# HF_Amp.net
KiCad netlist of a schematic drawn in Altium Designer
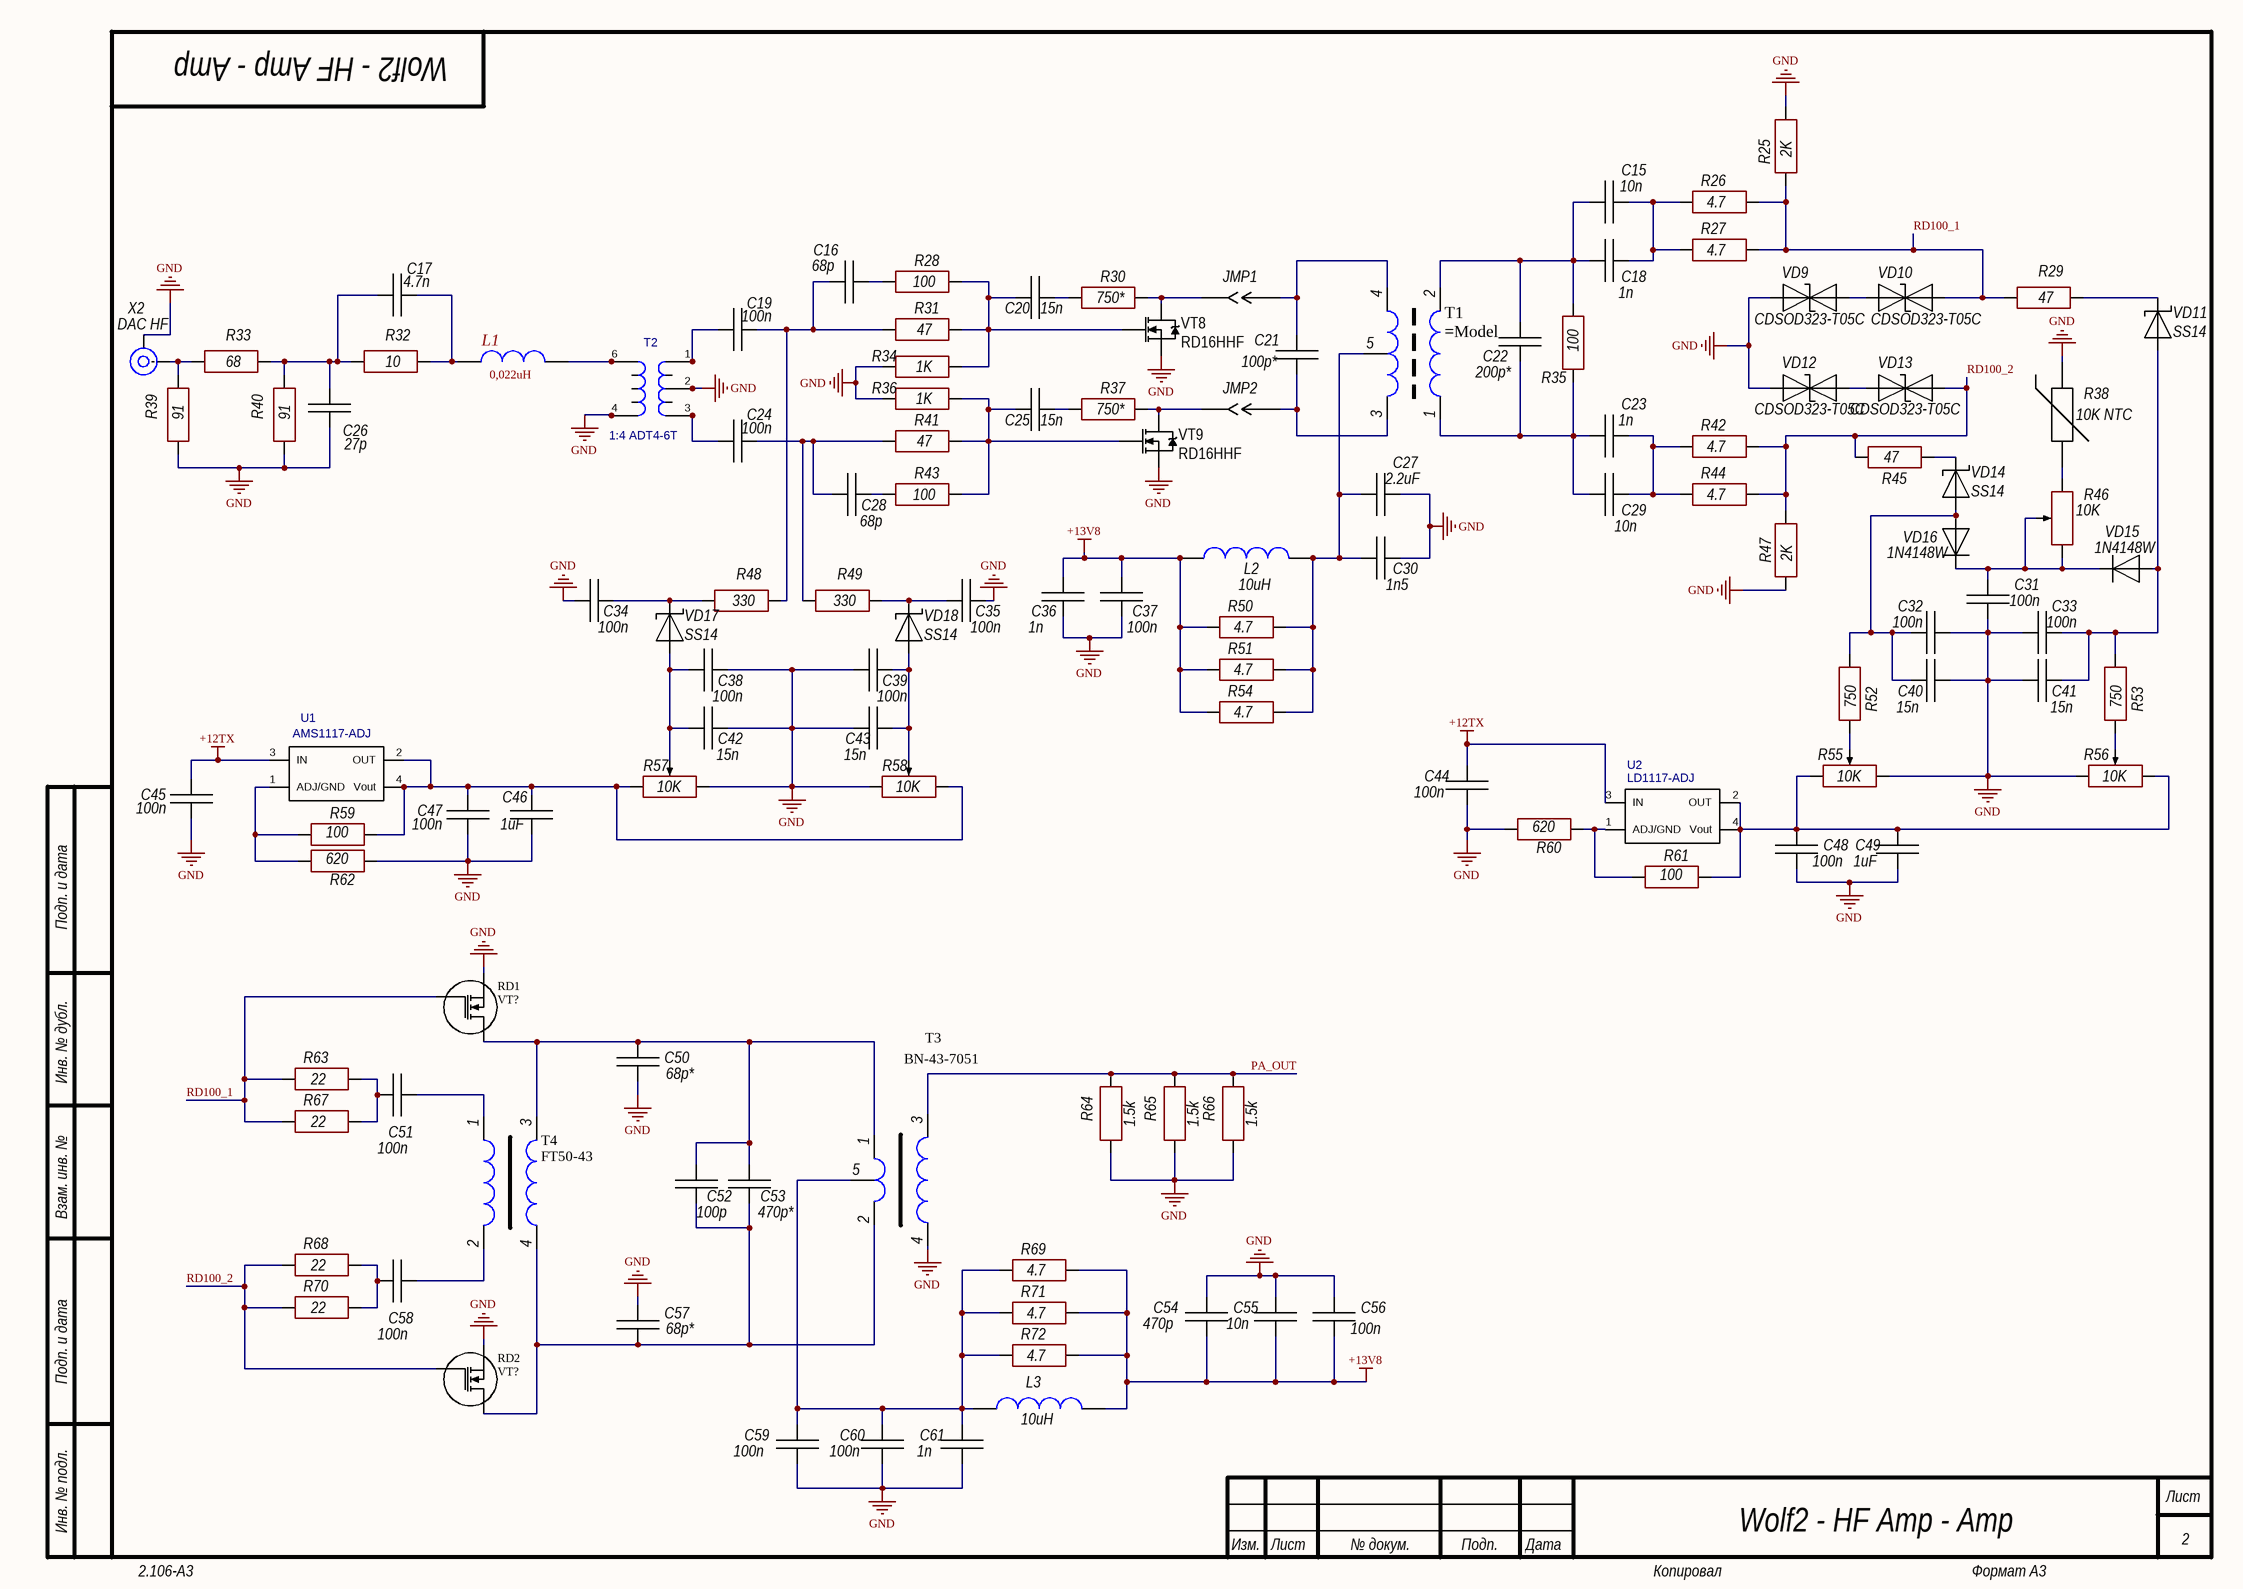
[diagram p0: HF_Amp.SchDoc]

(export (version "E")
  (design (tool "Eeschema 10.0.6"))
  (components
    (comp (ref "C15")
      (value "10n")
      (footprint "standard:CH1210C")
      (libsource (lib "Discrete") (part "Capacitor"))
    )
    (comp (ref "C16")
      (value "68p")
      (footprint "standard:CH0805C")
      (libsource (lib "Discrete") (part "Capacitor"))
    )
    (comp (ref "C17")
      (value "4.7n")
      (footprint "standard:CH0805C")
      (libsource (lib "Discrete") (part "Capacitor"))
    )
    (comp (ref "C18")
      (value "1n")
      (footprint "standard:CH1210C")
      (libsource (lib "Discrete") (part "Capacitor"))
    )
    (comp (ref "C19")
      (value "100n")
      (footprint "standard:CH0805C")
      (libsource (lib "Discrete") (part "Capacitor"))
    )
    (comp (ref "C20")
      (value "15n")
      (footprint "standard:CH1206C")
      (libsource (lib "Discrete") (part "Capacitor"))
    )
    (comp (ref "C21")
      (value "100p*")
      (footprint "standard:CH1210C")
      (libsource (lib "Discrete") (part "Capacitor"))
    )
    (comp (ref "C22")
      (value "200p*")
      (footprint "standard:CH1812C")
      (libsource (lib "Discrete") (part "Capacitor"))
    )
    (comp (ref "C23")
      (value "1n")
      (footprint "standard:CH1210C")
      (libsource (lib "Discrete") (part "Capacitor"))
    )
    (comp (ref "C24")
      (value "100n")
      (footprint "standard:CH0805C")
      (libsource (lib "Discrete") (part "Capacitor"))
    )
    (comp (ref "C25")
      (value "15n")
      (footprint "standard:CH1206C")
      (libsource (lib "Discrete") (part "Capacitor"))
    )
    (comp (ref "C26")
      (value "27p")
      (footprint "standard:CH0805C")
      (libsource (lib "Discrete") (part "Capacitor"))
    )
    (comp (ref "C27")
      (value "2.2uF")
      (footprint "standard:CH1206C")
      (libsource (lib "Discrete") (part "Capacitor"))
    )
    (comp (ref "C28")
      (value "68p")
      (footprint "standard:CH0805C")
      (libsource (lib "Discrete") (part "Capacitor"))
    )
    (comp (ref "C29")
      (value "10n")
      (footprint "standard:CH1210C")
      (libsource (lib "Discrete") (part "Capacitor"))
    )
    (comp (ref "C30")
      (value "1n5")
      (footprint "standard:CH1206C")
      (libsource (lib "Discrete") (part "Capacitor"))
    )
    (comp (ref "C31")
      (value "100n")
      (footprint "standard:CH0805C")
      (libsource (lib "Discrete") (part "Capacitor"))
    )
    (comp (ref "C32")
      (value "100n")
      (footprint "standard:CH0805C")
      (libsource (lib "Discrete") (part "Capacitor"))
    )
    (comp (ref "C33")
      (value "100n")
      (footprint "standard:CH0805C")
      (libsource (lib "Discrete") (part "Capacitor"))
    )
    (comp (ref "C34")
      (value "100n")
      (footprint "standard:CH0805C")
      (libsource (lib "Discrete") (part "Capacitor"))
    )
    (comp (ref "C35")
      (value "100n")
      (footprint "standard:CH0805C")
      (libsource (lib "Discrete") (part "Capacitor"))
    )
    (comp (ref "C36")
      (value "1n")
      (footprint "standard:CH0805C")
      (libsource (lib "Discrete") (part "Capacitor"))
    )
    (comp (ref "C37")
      (value "100n")
      (footprint "standard:CH0805C")
      (libsource (lib "Discrete") (part "Capacitor"))
    )
    (comp (ref "C38")
      (value "100n")
      (footprint "standard:CH0805C")
      (libsource (lib "Discrete") (part "Capacitor"))
    )
    (comp (ref "C39")
      (value "100n")
      (footprint "standard:CH0805C")
      (libsource (lib "Discrete") (part "Capacitor"))
    )
    (comp (ref "C40")
      (value "15n")
      (footprint "standard:CH0805C")
      (libsource (lib "Discrete") (part "Capacitor"))
    )
    (comp (ref "C41")
      (value "15n")
      (footprint "standard:CH0805C")
      (libsource (lib "Discrete") (part "Capacitor"))
    )
    (comp (ref "C42")
      (value "15n")
      (footprint "standard:CH0805C")
      (libsource (lib "Discrete") (part "Capacitor"))
    )
    (comp (ref "C43")
      (value "15n")
      (footprint "standard:CH0805C")
      (libsource (lib "Discrete") (part "Capacitor"))
    )
    (comp (ref "C44")
      (value "100n")
      (footprint "standard:CH0805C")
      (libsource (lib "Discrete") (part "Capacitor"))
    )
    (comp (ref "C45")
      (value "100n")
      (footprint "standard:CH0805C")
      (libsource (lib "Discrete") (part "Capacitor"))
    )
    (comp (ref "C46")
      (value "1uF")
      (footprint "standard:CH0805C")
      (libsource (lib "Discrete") (part "Capacitor"))
    )
    (comp (ref "C47")
      (value "100n")
      (footprint "standard:CH0805C")
      (libsource (lib "Discrete") (part "Capacitor"))
    )
    (comp (ref "C48")
      (value "100n")
      (footprint "standard:CH0805C")
      (libsource (lib "Discrete") (part "Capacitor"))
    )
    (comp (ref "C49")
      (value "1uF")
      (footprint "standard:CH0805C")
      (libsource (lib "Discrete") (part "Capacitor"))
    )
    (comp (ref "C50") (value "68p*") (footprint "CH1206ATC") (libsource (lib "Discrete") (part "Capacitor")))
    (comp (ref "C51")
      (value "100n")
      (footprint "standard:CH1210C")
      (libsource (lib "Discrete") (part "Capacitor"))
    )
    (comp (ref "C52")
      (value "100p")
      (footprint "standard:CH1812C")
      (libsource (lib "Discrete") (part "Capacitor"))
    )
    (comp (ref "C53")
      (value "470p*")
      (footprint "standard:CH1812C")
      (libsource (lib "Discrete") (part "Capacitor"))
    )
    (comp (ref "C54")
      (value "470p")
      (footprint "standard:CH1206C")
      (libsource (lib "Discrete") (part "Capacitor"))
    )
    (comp (ref "C55")
      (value "10n")
      (footprint "standard:CH1206C")
      (libsource (lib "Discrete") (part "Capacitor"))
    )
    (comp (ref "C56")
      (value "100n")
      (footprint "standard:CH1206C")
      (libsource (lib "Discrete") (part "Capacitor"))
    )
    (comp (ref "C57") (value "68p*") (footprint "CH1206ATC") (libsource (lib "Discrete") (part "Capacitor")))
    (comp (ref "C58")
      (value "100n")
      (footprint "standard:CH1210C")
      (libsource (lib "Discrete") (part "Capacitor"))
    )
    (comp (ref "C59")
      (value "100n")
      (footprint "standard:CH1206C")
      (libsource (lib "Discrete") (part "Capacitor"))
    )
    (comp (ref "C60")
      (value "100n")
      (footprint "standard:CH1206C")
      (libsource (lib "Discrete") (part "Capacitor"))
    )
    (comp (ref "C61")
      (value "1n")
      (footprint "standard:CH1206C")
      (libsource (lib "Discrete") (part "Capacitor"))
    )
    (comp (ref "JMP1")
      (value "Jumper_2")
      (footprint "CON: JUMPER_2")
      (description "Jumper")
      (libsource (lib "Connectors") (part "Jumper_2"))
    )
    (comp (ref "JMP2")
      (value "Jumper_2")
      (footprint "CON: JUMPER_2")
      (description "Jumper")
      (libsource (lib "Connectors") (part "Jumper_2"))
    )
    (comp (ref "L1") (value "0,022uH") (footprint "CH1210L") (libsource (lib "Discrete") (part "Inductor-2")))
    (comp (ref "L2")
      (value "10uH")
      (footprint "custom:IND: R24")
      (libsource (lib "Transformers") (part "Inductor ring"))
    )
    (comp (ref "L3")
      (value "10uH")
      (footprint "custom:IND: R24")
      (libsource (lib "Transformers") (part "Inductor ring"))
    )
    (comp (ref "R25") (value "2K") (footprint "standard:CH2512R") (libsource (lib "") (part "Resistor_2")))
    (comp (ref "R26")
      (value "4.7")
      (footprint "standard:CH2512R")
      (libsource (lib "Discrete") (part "Resistor"))
    )
    (comp (ref "R27")
      (value "4.7")
      (footprint "standard:CH2512R")
      (libsource (lib "Discrete") (part "Resistor"))
    )
    (comp (ref "R28")
      (value "100")
      (footprint "standard:CH0805R")
      (libsource (lib "Discrete") (part "Resistor"))
    )
    (comp (ref "R29")
      (value "47")
      (footprint "standard:CH0805R")
      (libsource (lib "Discrete") (part "Resistor"))
    )
    (comp (ref "R30")
      (value "750*")
      (footprint "standard:CH1206R")
      (libsource (lib "Discrete") (part "Resistor"))
    )
    (comp (ref "R31")
      (value "47")
      (footprint "standard:CH0805R")
      (libsource (lib "Discrete") (part "Resistor"))
    )
    (comp (ref "R32")
      (value "10")
      (footprint "standard:CH0805R")
      (libsource (lib "Discrete") (part "Resistor"))
    )
    (comp (ref "R33")
      (value "68")
      (footprint "standard:CH0805R")
      (libsource (lib "Discrete") (part "Resistor"))
    )
    (comp (ref "R34")
      (value "1K")
      (footprint "standard:CH0805R")
      (libsource (lib "Discrete") (part "Resistor"))
    )
    (comp (ref "R35") (value "100") (footprint "standard:CH2512R") (libsource (lib "") (part "Resistor_2")))
    (comp (ref "R36")
      (value "1K")
      (footprint "standard:CH0805R")
      (libsource (lib "Discrete") (part "Resistor"))
    )
    (comp (ref "R37")
      (value "750*")
      (footprint "standard:CH1206R")
      (libsource (lib "Discrete") (part "Resistor"))
    )
    (comp (ref "R38") (value "10K NTC") (footprint "CON: PBS-2") (libsource (lib "Discrete") (part "NTC")))
    (comp (ref "R39") (value "91") (footprint "standard:CH0805R") (libsource (lib "") (part "Resistor_2")))
    (comp (ref "R40") (value "91") (footprint "standard:CH0805R") (libsource (lib "") (part "Resistor_2")))
    (comp (ref "R41")
      (value "47")
      (footprint "standard:CH0805R")
      (libsource (lib "Discrete") (part "Resistor"))
    )
    (comp (ref "R42")
      (value "4.7")
      (footprint "standard:CH2512R")
      (libsource (lib "Discrete") (part "Resistor"))
    )
    (comp (ref "R43")
      (value "100")
      (footprint "standard:CH0805R")
      (libsource (lib "Discrete") (part "Resistor"))
    )
    (comp (ref "R44")
      (value "4.7")
      (footprint "standard:CH2512R")
      (libsource (lib "Discrete") (part "Resistor"))
    )
    (comp (ref "R45") (value "47") (footprint "standard:CH0805R") (libsource (lib "") (part "Resistor_3")))
    (comp (ref "R46")
      (value "10K")
      (footprint "custom:RES: 3296W")
      (libsource (lib "") (part "ADJ resistor_1"))
    )
    (comp (ref "R47") (value "2K") (footprint "standard:CH2512R") (libsource (lib "") (part "Resistor_2")))
    (comp (ref "R48")
      (value "330")
      (footprint "standard:CH0805R")
      (libsource (lib "Discrete") (part "Resistor"))
    )
    (comp (ref "R49")
      (value "330")
      (footprint "standard:CH0805R")
      (libsource (lib "Discrete") (part "Resistor"))
    )
    (comp (ref "R50")
      (value "4.7")
      (footprint "standard:CH2512R")
      (libsource (lib "Discrete") (part "Resistor"))
    )
    (comp (ref "R51")
      (value "4.7")
      (footprint "standard:CH2512R")
      (libsource (lib "Discrete") (part "Resistor"))
    )
    (comp (ref "R52") (value "750") (footprint "standard:CH0805R") (libsource (lib "") (part "Resistor_2")))
    (comp (ref "R53") (value "750") (footprint "standard:CH0805R") (libsource (lib "") (part "Resistor_2")))
    (comp (ref "R54")
      (value "4.7")
      (footprint "standard:CH2512R")
      (libsource (lib "Discrete") (part "Resistor"))
    )
    (comp (ref "R55")
      (value "10K")
      (footprint "custom:RES: 3296W")
      (libsource (lib "Discrete") (part "ADJ resistor"))
    )
    (comp (ref "R56")
      (value "10K")
      (footprint "custom:RES: 3296W")
      (libsource (lib "Discrete") (part "ADJ resistor"))
    )
    (comp (ref "R57")
      (value "10K")
      (footprint "custom:RES: 3296W")
      (libsource (lib "Discrete") (part "ADJ resistor"))
    )
    (comp (ref "R58")
      (value "10K")
      (footprint "custom:RES: 3296W")
      (libsource (lib "Discrete") (part "ADJ resistor"))
    )
    (comp (ref "R59")
      (value "100")
      (footprint "standard:CH0805R")
      (libsource (lib "Discrete") (part "Resistor"))
    )
    (comp (ref "R60")
      (value "620")
      (footprint "standard:CH0805R")
      (libsource (lib "Discrete") (part "Resistor"))
    )
    (comp (ref "R61")
      (value "100")
      (footprint "standard:CH0805R")
      (libsource (lib "Discrete") (part "Resistor"))
    )
    (comp (ref "R62")
      (value "620")
      (footprint "standard:CH0805R")
      (libsource (lib "Discrete") (part "Resistor"))
    )
    (comp (ref "R63")
      (value "22")
      (footprint "standard:CH2512R")
      (libsource (lib "Discrete") (part "Resistor"))
    )
    (comp (ref "R64") (value "1.5k") (footprint "R-DIP") (libsource (lib "") (part "Resistor_1")))
    (comp (ref "R65") (value "1.5k") (footprint "R-DIP") (libsource (lib "") (part "Resistor_1")))
    (comp (ref "R66") (value "1.5k") (footprint "R-DIP") (libsource (lib "") (part "Resistor_1")))
    (comp (ref "R67")
      (value "22")
      (footprint "standard:CH2512R")
      (libsource (lib "Discrete") (part "Resistor"))
    )
    (comp (ref "R68")
      (value "22")
      (footprint "standard:CH2512R")
      (libsource (lib "Discrete") (part "Resistor"))
    )
    (comp (ref "R69")
      (value "4.7")
      (footprint "standard:CH2512R")
      (libsource (lib "Discrete") (part "Resistor"))
    )
    (comp (ref "R70")
      (value "22")
      (footprint "standard:CH2512R")
      (libsource (lib "Discrete") (part "Resistor"))
    )
    (comp (ref "R71")
      (value "4.7")
      (footprint "standard:CH2512R")
      (libsource (lib "Discrete") (part "Resistor"))
    )
    (comp (ref "R72")
      (value "4.7")
      (footprint "standard:CH2512R")
      (libsource (lib "Discrete") (part "Resistor"))
    )
    (comp (ref "RD1") (value "VT?") (footprint "RD100") (libsource (lib "Transistor") (part "N-1")))
    (comp (ref "RD2")
      (value "VT?")
      (footprint "RD100")
      (description "RD100")
      (libsource (lib "Transistor") (part "N-1"))
    )
    (comp (ref "T1")
      (value "~")
      (footprint "BN43-202-RD16")
      (libsource (lib "Transformers") (part "TRANS-RD16"))
    )
    (comp (ref "T2")
      (value "1:4 ADT4-6T")
      (footprint "TRANSF_ACORE2")
      (description "Transformer")
      (libsource (lib "MOTHERBOARD_1") (part "TRANSF_ACORE2"))
    )
    (comp (ref "T3")
      (value "BN-43-7051")
      (footprint "BN61-002-V1")
      (libsource (lib "Transformers") (part "BN-43-7051_1"))
    )
    (comp (ref "T4")
      (value "FT50-43")
      (footprint "TRANS OS W2")
      (libsource (lib "Transformers") (part "Trans_L"))
    )
    (comp (ref "U1")
      (value "AMS1117-ADJ")
      (footprint "LT1117CST-3.3")
      (description "LT1117CST-ADJ")
      (fields (field (name "Comment") "1117-ADJ"))
      (libsource (lib "*") (part "LT1117CST-3.3"))
    )
    (comp (ref "U2")
      (value "LD1117-ADJ")
      (footprint "LT1117CST-3.3_2")
      (description "LT1117CST-ADJ")
      (fields (field (name "Comment") "1117-ADJ"))
      (libsource (lib "*") (part "LT1117CST-3.3"))
    )
    (comp (ref "VD9")
      (value "CDSOD323-T05C")
      (footprint "standard:SOD323")
      (libsource (lib "Diods") (part "TVS-diod"))
    )
    (comp (ref "VD10")
      (value "CDSOD323-T05C")
      (footprint "standard:SOD323")
      (libsource (lib "Diods") (part "TVS-diod"))
    )
    (comp (ref "VD11")
      (value "SS14")
      (footprint "standard:SMA")
      (libsource (lib "Diods") (part "Diod Schottky"))
    )
    (comp (ref "VD12")
      (value "CDSOD323-T05C")
      (footprint "standard:SOD323")
      (libsource (lib "Diods") (part "TVS-diod"))
    )
    (comp (ref "VD13")
      (value "CDSOD323-T05C")
      (footprint "standard:SOD323")
      (libsource (lib "Diods") (part "TVS-diod"))
    )
    (comp (ref "VD14")
      (value "SS14")
      (footprint "standard:SMA")
      (libsource (lib "Diods") (part "Diod Schottky"))
    )
    (comp (ref "VD15")
      (value "1N4148W")
      (footprint "standard:SOD123")
      (libsource (lib "Diods") (part "Diod"))
    )
    (comp (ref "VD16")
      (value "1N4148W")
      (footprint "standard:SOD123")
      (libsource (lib "Diods") (part "Diod"))
    )
    (comp (ref "VD17")
      (value "SS14")
      (footprint "standard:SMA")
      (libsource (lib "Diods") (part "Diod Schottky"))
    )
    (comp (ref "VD18")
      (value "SS14")
      (footprint "standard:SMA")
      (libsource (lib "Diods") (part "Diod Schottky"))
    )
    (comp (ref "VT8")
      (value "~")
      (footprint "rd16")
      (fields
        (field (name "MANUFACTURER") "Infineon Technologies")
        (field (name "VALUEMANUFACTURERPARTNUMBER") "MOSFET N-channel transistor, 80V, 7A, 9.1nC, 2.5W, 34mOhm, 756pF, 8-TDSON, -55...+150°C")
        (field (name "PARTNUMBER") "RD16HHF")
      )
      (libsource (lib "Transistor") (part "MOSFET_N_132"))
    )
    (comp (ref "VT9")
      (value "~")
      (footprint "rd16")
      (fields
        (field (name "MANUFACTURER") "Infineon Technologies")
        (field (name "VALUEMANUFACTURERPARTNUMBER") "MOSFET N-channel transistor, 80V, 7A, 9.1nC, 2.5W, 34mOhm, 756pF, 8-TDSON, -55...+150°C")
        (field (name "PARTNUMBER") "RD16HHF")
      )
      (libsource (lib "Transistor") (part "MOSFET_N_132"))
    )
    (comp (ref "X2")
      (value "DAC HF")
      (footprint "custom:CON: SMA")
      (description "RF")
      (libsource (lib "Connectors") (part "SMA"))
    )
  )
  (nets
    (net (code "1") (name "+12TX") (class "Default")
      (node (ref "C44") (pin "1") (pinfunction "1_1") (pintype "power_in"))
      (node (ref "C45") (pin "1") (pinfunction "1_1") (pintype "power_in"))
      (node (ref "U1") (pin "3") (pinfunction "IN_3") (pintype "passive"))
      (node (ref "U2") (pin "3") (pinfunction "IN_3") (pintype "passive"))
    )
    (net (code "2") (name "+13V8") (class "Default")
      (node (ref "C36") (pin "1") (pinfunction "1_1") (pintype "power_in"))
      (node (ref "C37") (pin "1") (pinfunction "1_1") (pintype "power_in"))
      (node (ref "C54") (pin "1") (pinfunction "1_1") (pintype "power_in"))
      (node (ref "C55") (pin "1") (pinfunction "1_1") (pintype "power_in"))
      (node (ref "C56") (pin "1") (pinfunction "1_1") (pintype "power_in"))
      (node (ref "L2") (pin "2") (pinfunction "2_2") (pintype "passive"))
      (node (ref "L3") (pin "1") (pinfunction "1_1") (pintype "passive"))
      (node (ref "R50") (pin "2") (pinfunction "2_2") (pintype "passive"))
      (node (ref "R51") (pin "2") (pinfunction "2_2") (pintype "passive"))
      (node (ref "R54") (pin "2") (pinfunction "2_2") (pintype "passive"))
      (node (ref "R69") (pin "1") (pinfunction "1_1") (pintype "passive"))
      (node (ref "R71") (pin "1") (pinfunction "1_1") (pintype "passive"))
      (node (ref "R72") (pin "1") (pinfunction "1_1") (pintype "passive"))
    )
    (net (code "3") (name "/PA_OUT") (class "Default")
      (node (ref "R64") (pin "2") (pinfunction "2_2") (pintype "passive"))
      (node (ref "R65") (pin "2") (pinfunction "2_2") (pintype "passive"))
      (node (ref "R66") (pin "2") (pinfunction "2_2") (pintype "passive"))
      (node (ref "T3") (pin "3") (pinfunction "3_3") (pintype "passive"))
    )
    (net (code "4") (name "/RD100_1") (class "Default")
      (node (ref "R25") (pin "2") (pinfunction "2_2") (pintype "passive"))
      (node (ref "R26") (pin "1") (pinfunction "1_1") (pintype "passive"))
      (node (ref "R27") (pin "1") (pinfunction "1_1") (pintype "passive"))
      (node (ref "R29") (pin "2") (pinfunction "2_2") (pintype "passive"))
      (node (ref "R63") (pin "2") (pinfunction "2_2") (pintype "passive"))
      (node (ref "R67") (pin "2") (pinfunction "2_2") (pintype "passive"))
      (node (ref "RD1") (pin "3") (pinfunction "G_3") (pintype "passive"))
      (node (ref "VD10") (pin "2") (pinfunction "C_2") (pintype "passive"))
    )
    (net (code "5") (name "/RD100_2") (class "Default")
      (node (ref "R42") (pin "1") (pinfunction "1_1") (pintype "passive"))
      (node (ref "R44") (pin "1") (pinfunction "1_1") (pintype "passive"))
      (node (ref "R45") (pin "1") (pinfunction "1_1") (pintype "passive"))
      (node (ref "R47") (pin "1") (pinfunction "1_1") (pintype "passive"))
      (node (ref "R68") (pin "2") (pinfunction "2_2") (pintype "passive"))
      (node (ref "R70") (pin "2") (pinfunction "2_2") (pintype "passive"))
      (node (ref "RD2") (pin "3") (pinfunction "G_3") (pintype "passive"))
      (node (ref "VD13") (pin "2") (pinfunction "C_2") (pintype "passive"))
    )
    (net (code "6") (name "GND") (class "Default")
      (node (ref "C26") (pin "1") (pinfunction "1_1") (pintype "power_in"))
      (node (ref "C27") (pin "2") (pinfunction "2_2") (pintype "power_in"))
      (node (ref "C30") (pin "2") (pinfunction "2_2") (pintype "power_in"))
      (node (ref "C31") (pin "2") (pinfunction "2_2") (pintype "power_in"))
      (node (ref "C32") (pin "1") (pinfunction "1_1") (pintype "power_in"))
      (node (ref "C33") (pin "2") (pinfunction "2_2") (pintype "power_in"))
      (node (ref "C34") (pin "2") (pinfunction "2_2") (pintype "power_in"))
      (node (ref "C35") (pin "1") (pinfunction "1_1") (pintype "power_in"))
      (node (ref "C36") (pin "2") (pinfunction "2_2") (pintype "power_in"))
      (node (ref "C37") (pin "2") (pinfunction "2_2") (pintype "power_in"))
      (node (ref "C38") (pin "1") (pinfunction "1_1") (pintype "power_in"))
      (node (ref "C39") (pin "2") (pinfunction "2_2") (pintype "power_in"))
      (node (ref "C40") (pin "1") (pinfunction "1_1") (pintype "power_in"))
      (node (ref "C41") (pin "2") (pinfunction "2_2") (pintype "power_in"))
      (node (ref "C42") (pin "1") (pinfunction "1_1") (pintype "power_in"))
      (node (ref "C43") (pin "2") (pinfunction "2_2") (pintype "power_in"))
      (node (ref "C44") (pin "2") (pinfunction "2_2") (pintype "power_in"))
      (node (ref "C45") (pin "2") (pinfunction "2_2") (pintype "power_in"))
      (node (ref "C46") (pin "2") (pinfunction "2_2") (pintype "power_in"))
      (node (ref "C47") (pin "2") (pinfunction "2_2") (pintype "power_in"))
      (node (ref "C48") (pin "2") (pinfunction "2_2") (pintype "power_in"))
      (node (ref "C49") (pin "2") (pinfunction "2_2") (pintype "power_in"))
      (node (ref "C50") (pin "1") (pinfunction "1_1") (pintype "power_in"))
      (node (ref "C54") (pin "2") (pinfunction "2_2") (pintype "power_in"))
      (node (ref "C55") (pin "2") (pinfunction "2_2") (pintype "power_in"))
      (node (ref "C56") (pin "2") (pinfunction "2_2") (pintype "power_in"))
      (node (ref "C57") (pin "2") (pinfunction "2_2") (pintype "power_in"))
      (node (ref "C59") (pin "1") (pinfunction "1_1") (pintype "power_in"))
      (node (ref "C60") (pin "1") (pinfunction "1_1") (pintype "power_in"))
      (node (ref "C61") (pin "1") (pinfunction "1_1") (pintype "power_in"))
      (node (ref "R25") (pin "1") (pinfunction "1_1") (pintype "passive"))
      (node (ref "R34") (pin "2") (pinfunction "2_2") (pintype "passive"))
      (node (ref "R36") (pin "2") (pinfunction "2_2") (pintype "passive"))
      (node (ref "R38") (pin "2") (pinfunction "2_2") (pintype "passive"))
      (node (ref "R39") (pin "2") (pinfunction "2_2") (pintype "passive"))
      (node (ref "R40") (pin "2") (pinfunction "2_2") (pintype "passive"))
      (node (ref "R47") (pin "2") (pinfunction "2_2") (pintype "passive"))
      (node (ref "R55") (pin "3") (pinfunction "3_3") (pintype "passive"))
      (node (ref "R56") (pin "1") (pinfunction "1_1") (pintype "passive"))
      (node (ref "R57") (pin "3") (pinfunction "3_3") (pintype "passive"))
      (node (ref "R58") (pin "1") (pinfunction "1_1") (pintype "passive"))
      (node (ref "R60") (pin "2") (pinfunction "2_2") (pintype "passive"))
      (node (ref "R62") (pin "1") (pinfunction "1_1") (pintype "passive"))
      (node (ref "R64") (pin "1") (pinfunction "1_1") (pintype "passive"))
      (node (ref "R65") (pin "1") (pinfunction "1_1") (pintype "passive"))
      (node (ref "R66") (pin "1") (pinfunction "1_1") (pintype "passive"))
      (node (ref "RD1") (pin "2") (pinfunction "S_2") (pintype "passive"))
      (node (ref "RD2") (pin "2") (pinfunction "S_2") (pintype "passive"))
      (node (ref "T2") (pin "11") (pinfunction "0_11") (pintype "passive"))
      (node (ref "T2") (pin "2") (pinfunction "S2_2") (pintype "passive"))
      (node (ref "T2") (pin "4") (pinfunction "P1_4") (pintype "passive"))
      (node (ref "T2") (pin "8") (pinfunction "0_8") (pintype "passive"))
      (node (ref "T3") (pin "4") (pinfunction "4_4") (pintype "passive"))
      (node (ref "VD12") (pin "1") (pinfunction "A_1") (pintype "passive"))
      (node (ref "VD9") (pin "1") (pinfunction "A_1") (pintype "passive"))
      (node (ref "VT8") (pin "2") (pinfunction "S_2") (pintype "passive"))
      (node (ref "VT9") (pin "2") (pinfunction "S_2") (pintype "passive"))
      (node (ref "X2") (pin "2") (pinfunction "IN_2") (pintype "passive"))
    )
    (net (code "7") (name "Net-(C15-Pad1)") (class "Default")
      (node (ref "C15") (pin "1") (pinfunction "1_1") (pintype "power_in"))
      (node (ref "C18") (pin "1") (pinfunction "1_1") (pintype "power_in"))
      (node (ref "C22") (pin "1") (pinfunction "1_1") (pintype "power_in"))
      (node (ref "R35") (pin "1") (pinfunction "1_1") (pintype "passive"))
      (node (ref "T1") (pin "2") (pinfunction "2_2") (pintype "passive"))
    )
    (net (code "8") (name "Net-(C15-Pad2)") (class "Default")
      (node (ref "C15") (pin "2") (pinfunction "2_2") (pintype "power_in"))
      (node (ref "C18") (pin "2") (pinfunction "2_2") (pintype "power_in"))
      (node (ref "R26") (pin "2") (pinfunction "2_2") (pintype "passive"))
      (node (ref "R27") (pin "2") (pinfunction "2_2") (pintype "passive"))
    )
    (net (code "9") (name "Net-(C16-Pad1)") (class "Default")
      (node (ref "C16") (pin "1") (pinfunction "1_1") (pintype "power_in"))
      (node (ref "R28") (pin "2") (pinfunction "2_2") (pintype "passive"))
    )
    (net (code "10") (name "Net-(C16-Pad2)") (class "Default")
      (node (ref "C16") (pin "2") (pinfunction "2_2") (pintype "power_in"))
      (node (ref "C19") (pin "2") (pinfunction "2_2") (pintype "power_in"))
      (node (ref "R31") (pin "2") (pinfunction "2_2") (pintype "passive"))
      (node (ref "R48") (pin "1") (pinfunction "1_1") (pintype "passive"))
    )
    (net (code "11") (name "Net-(C17-Pad1)") (class "Default")
      (node (ref "C17") (pin "1") (pinfunction "1_1") (pintype "power_in"))
      (node (ref "C26") (pin "2") (pinfunction "2_2") (pintype "power_in"))
      (node (ref "R32") (pin "2") (pinfunction "2_2") (pintype "passive"))
      (node (ref "R33") (pin "1") (pinfunction "1_1") (pintype "passive"))
      (node (ref "R40") (pin "1") (pinfunction "1_1") (pintype "passive"))
    )
    (net (code "12") (name "Net-(C17-Pad2)") (class "Default")
      (node (ref "C17") (pin "2") (pinfunction "2_2") (pintype "power_in"))
      (node (ref "L1") (pin "2") (pinfunction "2_2") (pintype "passive"))
      (node (ref "R32") (pin "1") (pinfunction "1_1") (pintype "passive"))
    )
    (net (code "13") (name "Net-(C20-Pad1)") (class "Default")
      (node (ref "C20") (pin "1") (pinfunction "1_1") (pintype "power_in"))
      (node (ref "R30") (pin "2") (pinfunction "2_2") (pintype "passive"))
    )
    (net (code "14") (name "Net-(C22-Pad2)") (class "Default")
      (node (ref "C22") (pin "2") (pinfunction "2_2") (pintype "power_in"))
      (node (ref "C23") (pin "1") (pinfunction "1_1") (pintype "power_in"))
      (node (ref "C29") (pin "1") (pinfunction "1_1") (pintype "power_in"))
      (node (ref "R35") (pin "2") (pinfunction "2_2") (pintype "passive"))
      (node (ref "T1") (pin "1") (pinfunction "1_1") (pintype "passive"))
    )
    (net (code "15") (name "Net-(C23-Pad2)") (class "Default")
      (node (ref "C23") (pin "2") (pinfunction "2_2") (pintype "power_in"))
      (node (ref "C29") (pin "2") (pinfunction "2_2") (pintype "power_in"))
      (node (ref "R42") (pin "2") (pinfunction "2_2") (pintype "passive"))
      (node (ref "R44") (pin "2") (pinfunction "2_2") (pintype "passive"))
    )
    (net (code "16") (name "Net-(C24-Pad2)") (class "Default")
      (node (ref "C24") (pin "2") (pinfunction "2_2") (pintype "power_in"))
      (node (ref "C28") (pin "2") (pinfunction "2_2") (pintype "power_in"))
      (node (ref "R41") (pin "2") (pinfunction "2_2") (pintype "passive"))
      (node (ref "R49") (pin "2") (pinfunction "2_2") (pintype "passive"))
    )
    (net (code "17") (name "Net-(C25-Pad1)") (class "Default")
      (node (ref "C25") (pin "1") (pinfunction "1_1") (pintype "power_in"))
      (node (ref "R37") (pin "2") (pinfunction "2_2") (pintype "passive"))
    )
    (net (code "18") (name "Net-(C27-Pad1)") (class "Default")
      (node (ref "C27") (pin "1") (pinfunction "1_1") (pintype "power_in"))
      (node (ref "C30") (pin "1") (pinfunction "1_1") (pintype "power_in"))
      (node (ref "L2") (pin "1") (pinfunction "1_1") (pintype "passive"))
      (node (ref "R50") (pin "1") (pinfunction "1_1") (pintype "passive"))
      (node (ref "R51") (pin "1") (pinfunction "1_1") (pintype "passive"))
      (node (ref "R54") (pin "1") (pinfunction "1_1") (pintype "passive"))
      (node (ref "T1") (pin "5") (pinfunction "5_5") (pintype "passive"))
    )
    (net (code "19") (name "Net-(C28-Pad1)") (class "Default")
      (node (ref "C28") (pin "1") (pinfunction "1_1") (pintype "power_in"))
      (node (ref "R43") (pin "2") (pinfunction "2_2") (pintype "passive"))
    )
    (net (code "20") (name "Net-(C31-Pad1)") (class "Default")
      (node (ref "C31") (pin "1") (pinfunction "1_1") (pintype "power_in"))
      (node (ref "R46") (pin "1") (pinfunction "1_1") (pintype "passive"))
      (node (ref "R46") (pin "2") (pinfunction "2_2") (pintype "passive"))
      (node (ref "VD15") (pin "2") (pinfunction "2_2") (pintype "passive"))
      (node (ref "VD16") (pin "2") (pinfunction "2_2") (pintype "passive"))
    )
    (net (code "21") (name "Net-(C32-Pad2)") (class "Default")
      (node (ref "C32") (pin "2") (pinfunction "2_2") (pintype "power_in"))
      (node (ref "C40") (pin "2") (pinfunction "2_2") (pintype "power_in"))
      (node (ref "R52") (pin "1") (pinfunction "1_1") (pintype "passive"))
      (node (ref "VD14") (pin "1") (pinfunction "1_1") (pintype "passive"))
      (node (ref "VD16") (pin "1") (pinfunction "1_1") (pintype "passive"))
    )
    (net (code "22") (name "Net-(C33-Pad1)") (class "Default")
      (node (ref "C33") (pin "1") (pinfunction "1_1") (pintype "power_in"))
      (node (ref "C41") (pin "1") (pinfunction "1_1") (pintype "power_in"))
      (node (ref "R53") (pin "1") (pinfunction "1_1") (pintype "passive"))
      (node (ref "VD11") (pin "1") (pinfunction "1_1") (pintype "passive"))
      (node (ref "VD15") (pin "1") (pinfunction "1_1") (pintype "passive"))
    )
    (net (code "23") (name "Net-(C34-Pad1)") (class "Default")
      (node (ref "C34") (pin "1") (pinfunction "1_1") (pintype "power_in"))
      (node (ref "R48") (pin "2") (pinfunction "2_2") (pintype "passive"))
      (node (ref "VD17") (pin "2") (pinfunction "2_2") (pintype "passive"))
    )
    (net (code "24") (name "Net-(C35-Pad2)") (class "Default")
      (node (ref "C35") (pin "2") (pinfunction "2_2") (pintype "power_in"))
      (node (ref "R49") (pin "1") (pinfunction "1_1") (pintype "passive"))
      (node (ref "VD18") (pin "2") (pinfunction "2_2") (pintype "passive"))
    )
    (net (code "25") (name "Net-(C38-Pad2)") (class "Default")
      (node (ref "C38") (pin "2") (pinfunction "2_2") (pintype "power_in"))
      (node (ref "C42") (pin "2") (pinfunction "2_2") (pintype "power_in"))
      (node (ref "R57") (pin "2") (pinfunction "2_2") (pintype "passive"))
      (node (ref "VD17") (pin "1") (pinfunction "1_1") (pintype "passive"))
    )
    (net (code "26") (name "Net-(C39-Pad1)") (class "Default")
      (node (ref "C39") (pin "1") (pinfunction "1_1") (pintype "power_in"))
      (node (ref "C43") (pin "1") (pinfunction "1_1") (pintype "power_in"))
      (node (ref "R58") (pin "2") (pinfunction "2_2") (pintype "passive"))
      (node (ref "VD18") (pin "1") (pinfunction "1_1") (pintype "passive"))
    )
    (net (code "27") (name "Net-(C51-Pad1)") (class "Default")
      (node (ref "C51") (pin "1") (pinfunction "1_1") (pintype "power_in"))
      (node (ref "R63") (pin "1") (pinfunction "1_1") (pintype "passive"))
      (node (ref "R67") (pin "1") (pinfunction "1_1") (pintype "passive"))
    )
    (net (code "28") (name "Net-(C51-Pad2)") (class "Default")
      (node (ref "C51") (pin "2") (pinfunction "2_2") (pintype "power_in"))
      (node (ref "T4") (pin "1") (pinfunction "1_1") (pintype "passive"))
    )
    (net (code "29") (name "Net-(C58-Pad1)") (class "Default")
      (node (ref "C58") (pin "1") (pinfunction "1_1") (pintype "power_in"))
      (node (ref "R68") (pin "1") (pinfunction "1_1") (pintype "passive"))
      (node (ref "R70") (pin "1") (pinfunction "1_1") (pintype "passive"))
    )
    (net (code "30") (name "Net-(C58-Pad2)") (class "Default")
      (node (ref "C58") (pin "2") (pinfunction "2_2") (pintype "power_in"))
      (node (ref "T4") (pin "2") (pinfunction "2_2") (pintype "passive"))
    )
    (net (code "31") (name "Net-(C59-Pad2)") (class "Default")
      (node (ref "C59") (pin "2") (pinfunction "2_2") (pintype "power_in"))
      (node (ref "C60") (pin "2") (pinfunction "2_2") (pintype "power_in"))
      (node (ref "C61") (pin "2") (pinfunction "2_2") (pintype "power_in"))
      (node (ref "L3") (pin "2") (pinfunction "2_2") (pintype "passive"))
      (node (ref "R69") (pin "2") (pinfunction "2_2") (pintype "passive"))
      (node (ref "R71") (pin "2") (pinfunction "2_2") (pintype "passive"))
      (node (ref "R72") (pin "2") (pinfunction "2_2") (pintype "passive"))
      (node (ref "T3") (pin "5") (pinfunction "5_5") (pintype "passive"))
    )
    (net (code "32") (name "Net-(JMP1-IN)") (class "Default")
      (node (ref "JMP1") (pin "1") (pinfunction "IN_1") (pintype "passive"))
      (node (ref "R30") (pin "1") (pinfunction "1_1") (pintype "passive"))
      (node (ref "VT8") (pin "3") (pinfunction "D_3") (pintype "passive"))
    )
    (net (code "33") (name "Net-(JMP1-OUT)") (class "Default")
      (node (ref "C21") (pin "1") (pinfunction "1_1") (pintype "power_in"))
      (node (ref "JMP1") (pin "2") (pinfunction "OUT_2") (pintype "passive"))
      (node (ref "T1") (pin "4") (pinfunction "4_4") (pintype "passive"))
    )
    (net (code "34") (name "Net-(JMP2-IN)") (class "Default")
      (node (ref "JMP2") (pin "1") (pinfunction "IN_1") (pintype "passive"))
      (node (ref "R37") (pin "1") (pinfunction "1_1") (pintype "passive"))
      (node (ref "VT9") (pin "3") (pinfunction "D_3") (pintype "passive"))
    )
    (net (code "35") (name "Net-(JMP2-OUT)") (class "Default")
      (node (ref "C21") (pin "2") (pinfunction "2_2") (pintype "power_in"))
      (node (ref "JMP2") (pin "2") (pinfunction "OUT_2") (pintype "passive"))
      (node (ref "T1") (pin "3") (pinfunction "3_3") (pintype "passive"))
    )
    (net (code "36") (name "Net-(R29-Pad1)") (class "Default")
      (node (ref "R29") (pin "1") (pinfunction "1_1") (pintype "passive"))
      (node (ref "VD11") (pin "2") (pinfunction "2_2") (pintype "passive"))
    )
    (net (code "37") (name "Net-(R33-Pad2)") (class "Default")
      (node (ref "R33") (pin "2") (pinfunction "2_2") (pintype "passive"))
      (node (ref "R39") (pin "1") (pinfunction "1_1") (pintype "passive"))
      (node (ref "X2") (pin "1") (pinfunction "IN_1") (pintype "passive"))
    )
    (net (code "38") (name "Net-(R38-Pad1)") (class "Default")
      (node (ref "R38") (pin "1") (pinfunction "1_1") (pintype "passive"))
      (node (ref "R46") (pin "3") (pinfunction "3_3") (pintype "passive"))
    )
    (net (code "39") (name "Net-(R45-Pad2)") (class "Default")
      (node (ref "R45") (pin "2") (pinfunction "2_2") (pintype "passive"))
      (node (ref "VD14") (pin "2") (pinfunction "2_2") (pintype "passive"))
    )
    (net (code "40") (name "Net-(R52-Pad2)") (class "Default")
      (node (ref "R52") (pin "2") (pinfunction "2_2") (pintype "passive"))
      (node (ref "R55") (pin "2") (pinfunction "2_2") (pintype "passive"))
    )
    (net (code "41") (name "Net-(R53-Pad2)") (class "Default")
      (node (ref "R53") (pin "2") (pinfunction "2_2") (pintype "passive"))
      (node (ref "R56") (pin "2") (pinfunction "2_2") (pintype "passive"))
    )
    (net (code "42") (name "Net-(RD1-D)") (class "Default")
      (node (ref "C50") (pin "2") (pinfunction "2_2") (pintype "power_in"))
      (node (ref "C52") (pin "2") (pinfunction "2_2") (pintype "power_in"))
      (node (ref "C53") (pin "2") (pinfunction "2_2") (pintype "power_in"))
      (node (ref "RD1") (pin "1") (pinfunction "D_1") (pintype "passive"))
      (node (ref "T3") (pin "1") (pinfunction "1_1") (pintype "passive"))
      (node (ref "T4") (pin "3") (pinfunction "3_3") (pintype "passive"))
    )
    (net (code "43") (name "Net-(RD2-D)") (class "Default")
      (node (ref "C52") (pin "1") (pinfunction "1_1") (pintype "power_in"))
      (node (ref "C53") (pin "1") (pinfunction "1_1") (pintype "power_in"))
      (node (ref "C57") (pin "1") (pinfunction "1_1") (pintype "power_in"))
      (node (ref "RD2") (pin "1") (pinfunction "D_1") (pintype "passive"))
      (node (ref "T3") (pin "2") (pinfunction "2_2") (pintype "passive"))
      (node (ref "T4") (pin "4") (pinfunction "4_4") (pintype "passive"))
    )
    (net (code "44") (name "Net-(T2-P2)") (class "Default")
      (node (ref "L1") (pin "1") (pinfunction "1_1") (pintype "passive"))
      (node (ref "T2") (pin "10") (pinfunction "0_10") (pintype "passive"))
      (node (ref "T2") (pin "6") (pinfunction "P2_6") (pintype "passive"))
    )
    (net (code "45") (name "Net-(T2-S1)") (class "Default")
      (node (ref "C24") (pin "1") (pinfunction "1_1") (pintype "power_in"))
      (node (ref "T2") (pin "3") (pinfunction "S1_3") (pintype "passive"))
      (node (ref "T2") (pin "9") (pinfunction "0_9") (pintype "passive"))
    )
    (net (code "46") (name "Net-(T2-S3)") (class "Default")
      (node (ref "C19") (pin "1") (pinfunction "1_1") (pintype "power_in"))
      (node (ref "T2") (pin "1") (pinfunction "S3_1") (pintype "passive"))
      (node (ref "T2") (pin "7") (pinfunction "0_7") (pintype "passive"))
    )
    (net (code "47") (name "Net-(U1-ADJ{slash}GND)") (class "Default")
      (node (ref "R59") (pin "2") (pinfunction "2_2") (pintype "passive"))
      (node (ref "R62") (pin "2") (pinfunction "2_2") (pintype "passive"))
      (node (ref "U1") (pin "1") (pinfunction "ADJ/GND_1") (pintype "passive"))
    )
    (net (code "48") (name "Net-(U1-OUT)") (class "Default")
      (node (ref "C46") (pin "1") (pinfunction "1_1") (pintype "power_in"))
      (node (ref "C47") (pin "1") (pinfunction "1_1") (pintype "power_in"))
      (node (ref "R57") (pin "1") (pinfunction "1_1") (pintype "passive"))
      (node (ref "R58") (pin "3") (pinfunction "3_3") (pintype "passive"))
      (node (ref "R59") (pin "1") (pinfunction "1_1") (pintype "passive"))
      (node (ref "U1") (pin "2") (pinfunction "OUT_2") (pintype "passive"))
      (node (ref "U1") (pin "4") (pinfunction "Vout_4") (pintype "passive"))
    )
    (net (code "49") (name "Net-(U2-ADJ{slash}GND)") (class "Default")
      (node (ref "R60") (pin "1") (pinfunction "1_1") (pintype "passive"))
      (node (ref "R61") (pin "2") (pinfunction "2_2") (pintype "passive"))
      (node (ref "U2") (pin "1") (pinfunction "ADJ/GND_1") (pintype "passive"))
    )
    (net (code "50") (name "Net-(U2-OUT)") (class "Default")
      (node (ref "C48") (pin "1") (pinfunction "1_1") (pintype "power_in"))
      (node (ref "C49") (pin "1") (pinfunction "1_1") (pintype "power_in"))
      (node (ref "R55") (pin "1") (pinfunction "1_1") (pintype "passive"))
      (node (ref "R56") (pin "3") (pinfunction "3_3") (pintype "passive"))
      (node (ref "R61") (pin "1") (pinfunction "1_1") (pintype "passive"))
      (node (ref "U2") (pin "2") (pinfunction "OUT_2") (pintype "passive"))
      (node (ref "U2") (pin "4") (pinfunction "Vout_4") (pintype "passive"))
    )
    (net (code "51") (name "Net-(VD10-A)") (class "Default")
      (node (ref "VD10") (pin "1") (pinfunction "A_1") (pintype "passive"))
      (node (ref "VD9") (pin "2") (pinfunction "C_2") (pintype "passive"))
    )
    (net (code "52") (name "Net-(VD12-C)") (class "Default")
      (node (ref "VD12") (pin "2") (pinfunction "C_2") (pintype "passive"))
      (node (ref "VD13") (pin "1") (pinfunction "A_1") (pintype "passive"))
    )
    (net (code "53") (name "Net-(VT8-G)") (class "Default")
      (node (ref "C20") (pin "2") (pinfunction "2_2") (pintype "power_in"))
      (node (ref "R28") (pin "1") (pinfunction "1_1") (pintype "passive"))
      (node (ref "R31") (pin "1") (pinfunction "1_1") (pintype "passive"))
      (node (ref "R34") (pin "1") (pinfunction "1_1") (pintype "passive"))
      (node (ref "VT8") (pin "1") (pinfunction "G_1") (pintype "passive"))
    )
    (net (code "54") (name "Net-(VT9-G)") (class "Default")
      (node (ref "C25") (pin "2") (pinfunction "2_2") (pintype "power_in"))
      (node (ref "R36") (pin "1") (pinfunction "1_1") (pintype "passive"))
      (node (ref "R41") (pin "1") (pinfunction "1_1") (pintype "passive"))
      (node (ref "R43") (pin "1") (pinfunction "1_1") (pintype "passive"))
      (node (ref "VT9") (pin "1") (pinfunction "G_1") (pintype "passive"))
    )
  )
)
